# MCU.net
KiCad netlist of a schematic drawn in Altium Designer
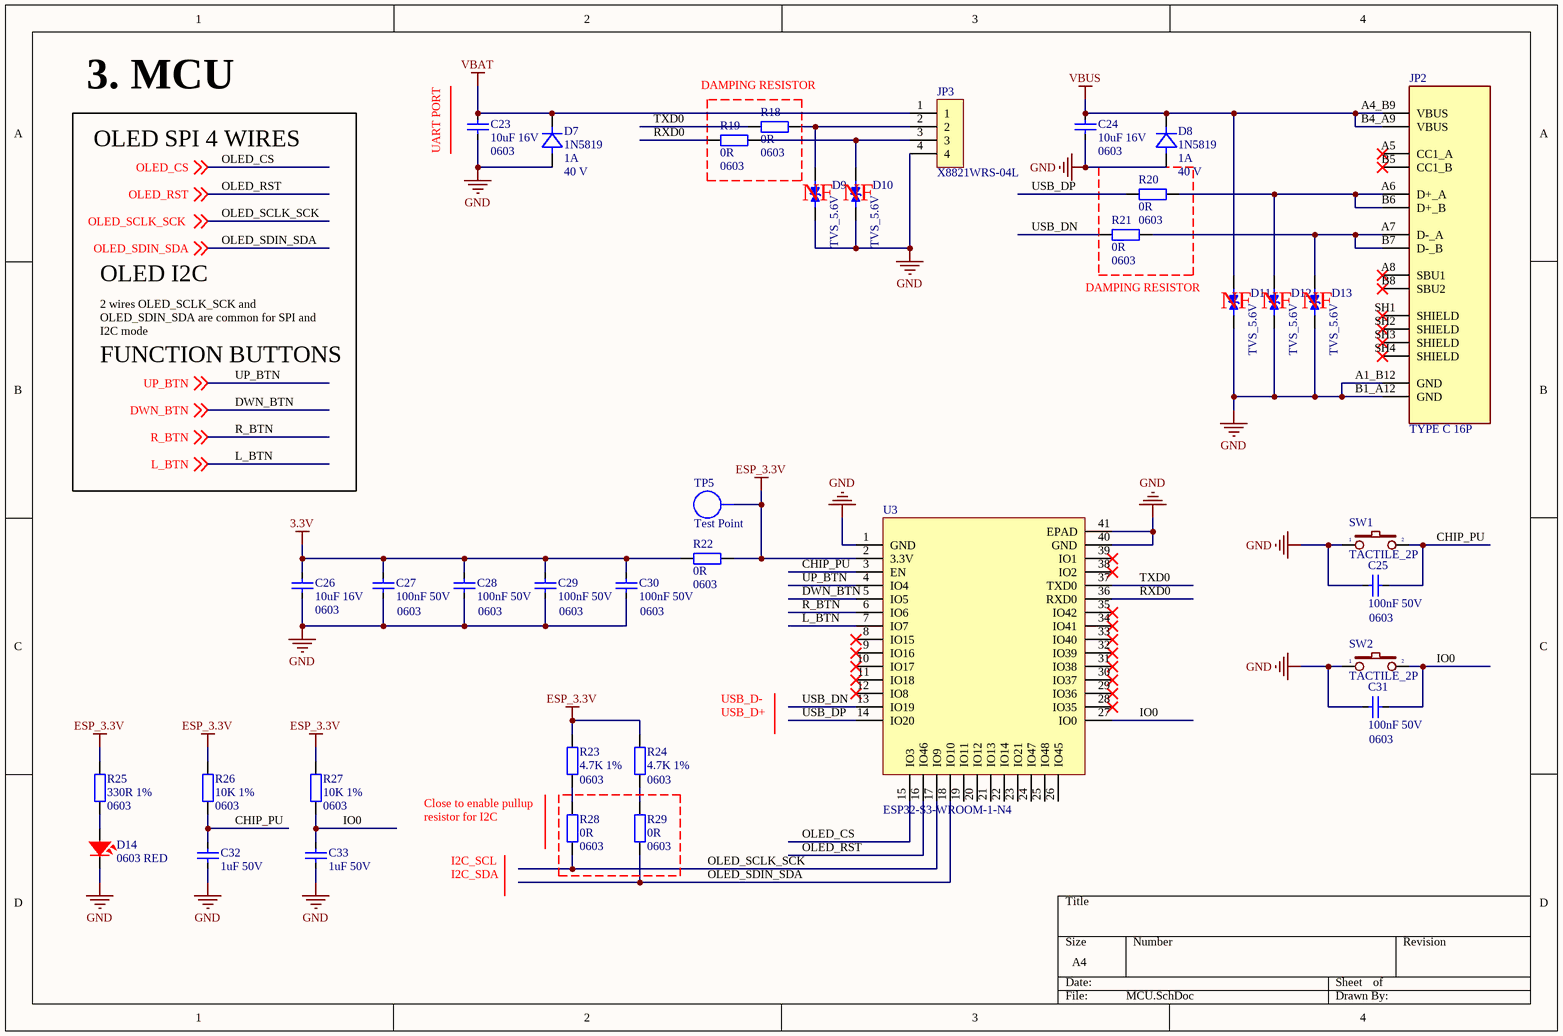
[diagram p0: MCU.SchDoc]

(export (version "E")
  (design (tool "Eeschema 10.0.6"))
  (components
    (comp (ref "C23")
      (value "10uF 16V")
      (footprint "CAP_SMD_0603")
      (description "10 µF ±20% 16V Ceramic Capacitor X6S 0603 (1608 Metric)")
      (fields
        (field (name "MANUFACTURER") "Murata Electronics")
        (field (name "MANUFACTURE PART NUMBER") "GRM188C81C106MA73D")
        (field (name "SIZE") "0603")
      )
      (libsource (lib "Capacitors") (part "C0603_MLCC_10uF_16V"))
    )
    (comp (ref "C24")
      (value "10uF 16V")
      (footprint "CAP_SMD_0603")
      (description "10 µF ±20% 16V Ceramic Capacitor X6S 0603 (1608 Metric)")
      (fields
        (field (name "MANUFACTURER") "Murata Electronics")
        (field (name "MANUFACTURE PART NUMBER") "GRM188C81C106MA73D")
        (field (name "SIZE") "0603")
      )
      (libsource (lib "Capacitors") (part "C0603_MLCC_10uF_16V"))
    )
    (comp (ref "C25")
      (value "100nF 50V")
      (footprint "CAP_SMD_0603")
      (description "0.1 µF ±10% 50V Ceramic Capacitor X7R 0603 (1608 Metric)")
      (fields
        (field (name "MANUFACTURER") "Samsung Electro-Mechanics")
        (field (name "MANUFACTURE PART NUMBER") "CL10B104KB8NNNC")
        (field (name "SIZE") "0603")
      )
      (libsource (lib "Capacitors") (part "C0603_MLCC_100nF_50V"))
    )
    (comp (ref "C26")
      (value "10uF 16V")
      (footprint "CAP_SMD_0603")
      (description "10 µF ±20% 16V Ceramic Capacitor X6S 0603 (1608 Metric)")
      (fields
        (field (name "MANUFACTURER") "Murata Electronics")
        (field (name "MANUFACTURE PART NUMBER") "GRM188C81C106MA73D")
        (field (name "SIZE") "0603")
      )
      (libsource (lib "Capacitors") (part "C0603_MLCC_10uF_16V"))
    )
    (comp (ref "C27")
      (value "100nF 50V")
      (footprint "CAP_SMD_0603")
      (description "0.1 µF ±10% 50V Ceramic Capacitor X7R 0603 (1608 Metric)")
      (fields
        (field (name "MANUFACTURER") "Samsung Electro-Mechanics")
        (field (name "MANUFACTURE PART NUMBER") "CL10B104KB8NNNC")
        (field (name "SIZE") "0603")
      )
      (libsource (lib "Capacitors") (part "C0603_MLCC_100nF_50V"))
    )
    (comp (ref "C28")
      (value "100nF 50V")
      (footprint "CAP_SMD_0603")
      (description "0.1 µF ±10% 50V Ceramic Capacitor X7R 0603 (1608 Metric)")
      (fields
        (field (name "MANUFACTURER") "Samsung Electro-Mechanics")
        (field (name "MANUFACTURE PART NUMBER") "CL10B104KB8NNNC")
        (field (name "SIZE") "0603")
      )
      (libsource (lib "Capacitors") (part "C0603_MLCC_100nF_50V"))
    )
    (comp (ref "C29")
      (value "100nF 50V")
      (footprint "CAP_SMD_0603")
      (description "0.1 µF ±10% 50V Ceramic Capacitor X7R 0603 (1608 Metric)")
      (fields
        (field (name "MANUFACTURER") "Samsung Electro-Mechanics")
        (field (name "MANUFACTURE PART NUMBER") "CL10B104KB8NNNC")
        (field (name "SIZE") "0603")
      )
      (libsource (lib "Capacitors") (part "C0603_MLCC_100nF_50V"))
    )
    (comp (ref "C30")
      (value "100nF 50V")
      (footprint "CAP_SMD_0603")
      (description "0.1 µF ±10% 50V Ceramic Capacitor X7R 0603 (1608 Metric)")
      (fields
        (field (name "MANUFACTURER") "Samsung Electro-Mechanics")
        (field (name "MANUFACTURE PART NUMBER") "CL10B104KB8NNNC")
        (field (name "SIZE") "0603")
      )
      (libsource (lib "Capacitors") (part "C0603_MLCC_100nF_50V"))
    )
    (comp (ref "C31")
      (value "100nF 50V")
      (footprint "CAP_SMD_0603")
      (description "0.1 µF ±10% 50V Ceramic Capacitor X7R 0603 (1608 Metric)")
      (fields
        (field (name "MANUFACTURER") "Samsung Electro-Mechanics")
        (field (name "MANUFACTURE PART NUMBER") "CL10B104KB8NNNC")
        (field (name "SIZE") "0603")
      )
      (libsource (lib "Capacitors") (part "C0603_MLCC_100nF_50V"))
    )
    (comp (ref "C32")
      (value "1uF 50V")
      (footprint "CAP_SMD_0603")
      (description "1 µF ±10% 50V Ceramic Capacitor X5R 0603 (1608 Metric)")
      (fields
        (field (name "MANUFACTURER") "Samsung Electro-Mechanics")
        (field (name "MANUFACTURE PART NUMBER") "CL10A105KB8NNNC")
      )
      (libsource (lib "Capacitors") (part "C0603_MLCC_1uF_50V"))
    )
    (comp (ref "C33")
      (value "1uF 50V")
      (footprint "CAP_SMD_0603")
      (description "1 µF ±10% 50V Ceramic Capacitor X5R 0603 (1608 Metric)")
      (fields
        (field (name "MANUFACTURER") "Samsung Electro-Mechanics")
        (field (name "MANUFACTURE PART NUMBER") "CL10A105KB8NNNC")
      )
      (libsource (lib "Capacitors") (part "C0603_MLCC_1uF_50V"))
    )
    (comp (ref "D7")
      (value "1N5819")
      (footprint "DIO-SMD-123")
      (description "Diode 40 V 1A Surface Mount SOD-123")
      (fields
        (field (name "MANUFACTURER") "Diodes Incorporated")
        (field (name "MANUFACTURE PART NUMBER") "1N5819HW-7-F")
        (field (name "CURRENT - AVERAGE RECTIFIED (IO)") "1A")
        (field (name "VOLTAGE - DC REVERSE (VR) (MAX)") "40 V")
      )
      (libsource (lib "Diode") (part "1N5819"))
    )
    (comp (ref "D8")
      (value "1N5819")
      (footprint "DIO-SMD-123")
      (description "Diode 40 V 1A Surface Mount SOD-123")
      (fields
        (field (name "MANUFACTURER") "Diodes Incorporated")
        (field (name "MANUFACTURE PART NUMBER") "1N5819HW-7-F")
        (field (name "CURRENT - AVERAGE RECTIFIED (IO)") "1A")
        (field (name "VOLTAGE - DC REVERSE (VR) (MAX)") "40 V")
      )
      (libsource (lib "Diode") (part "1N5819"))
    )
    (comp (ref "D9")
      (value "TVS_5.6V")
      (footprint "SOD_523")
      (description "9.4A 18.6V 5.6V Bi-Directional 5V SOD-523 Electrostatic and Surge Protection (TVS/ESD) ROHS")
      (fields (field (name "MANUFACTURER") "LRC") (field (name "MANUFACTURE PART NUMBER") "LESD5D5.0CT1G"))
      (libsource (lib "Diode") (part "TVS_5.6V"))
    )
    (comp (ref "D10")
      (value "TVS_5.6V")
      (footprint "SOD_523")
      (description "9.4A 18.6V 5.6V Bi-Directional 5V SOD-523 Electrostatic and Surge Protection (TVS/ESD) ROHS")
      (fields (field (name "MANUFACTURER") "LRC") (field (name "MANUFACTURE PART NUMBER") "LESD5D5.0CT1G"))
      (libsource (lib "Diode") (part "TVS_5.6V"))
    )
    (comp (ref "D11")
      (value "TVS_5.6V")
      (footprint "SOD_523")
      (description "9.4A 18.6V 5.6V Bi-Directional 5V SOD-523 Electrostatic and Surge Protection (TVS/ESD) ROHS")
      (fields (field (name "MANUFACTURER") "LRC") (field (name "MANUFACTURE PART NUMBER") "LESD5D5.0CT1G"))
      (libsource (lib "Diode") (part "TVS_5.6V"))
    )
    (comp (ref "D12")
      (value "TVS_5.6V")
      (footprint "SOD_523")
      (description "9.4A 18.6V 5.6V Bi-Directional 5V SOD-523 Electrostatic and Surge Protection (TVS/ESD) ROHS")
      (fields (field (name "MANUFACTURER") "LRC") (field (name "MANUFACTURE PART NUMBER") "LESD5D5.0CT1G"))
      (libsource (lib "Diode") (part "TVS_5.6V"))
    )
    (comp (ref "D13")
      (value "TVS_5.6V")
      (footprint "SOD_523")
      (description "9.4A 18.6V 5.6V Bi-Directional 5V SOD-523 Electrostatic and Surge Protection (TVS/ESD) ROHS")
      (fields (field (name "MANUFACTURER") "LRC") (field (name "MANUFACTURE PART NUMBER") "LESD5D5.0CT1G"))
      (libsource (lib "Diode") (part "TVS_5.6V"))
    )
    (comp (ref "D14")
      (value "0603 RED")
      (footprint "LED-0603")
      (description "Red 625nm LED Indication - Discrete 2V 0603 (1608 Metric)")
      (fields
        (field (name "MANUFACTURER") "Würth Elektronik")
        (field (name "MANUFACTURE PART NUMBER") "150060RS75000")
      )
      (libsource (lib "LEDs") (part "LED_0603_RED"))
    )
    (comp (ref "JP2")
      (value "TYPE C 16P")
      (footprint "TYPE C 16P")
      (fields
        (field (name "MANUFACTURER") "Amphenol ICC (Commercial Products)")
        (field (name "MANUFACTURE PART NUMBER") "12402012E212A")
      )
      (libsource (lib "Connectors") (part "TYPE_C_16P"))
    )
    (comp (ref "JP3")
      (value "X8821WRS-04L")
      (footprint "CONN_X8821WRS-04L-LPSN")
      (fields
        (field (name "MANUFACTURER") "XKB Connection")
        (field (name "MANUFACTURE PART NUMBER") "X8821WRS-04-9TSN")
      )
      (libsource (lib "Connectors") (part "X8821WRS-04L"))
    )
    (comp (ref "R18")
      (value "0R")
      (footprint "RES_SMD_0603")
      (description "0 Ohms Jumper Chip Resistor 0603 (1608 Metric) Automotive AEC-Q200 Thick Film")
      (fields
        (field (name "MANUFACTURER") "Stackpole Electronics Inc")
        (field (name "MANUFACTURE PART NUMBER") "RMCF0603ZT0R00")
        (field (name "SIZE") "0603")
      )
      (libsource (lib "Resistors") (part "R0603_0R"))
    )
    (comp (ref "R19")
      (value "0R")
      (footprint "RES_SMD_0603")
      (description "0 Ohms Jumper Chip Resistor 0603 (1608 Metric) Automotive AEC-Q200 Thick Film")
      (fields
        (field (name "MANUFACTURER") "Stackpole Electronics Inc")
        (field (name "MANUFACTURE PART NUMBER") "RMCF0603ZT0R00")
        (field (name "SIZE") "0603")
      )
      (libsource (lib "Resistors") (part "R0603_0R"))
    )
    (comp (ref "R20")
      (value "0R")
      (footprint "RES_SMD_0603")
      (description "0 Ohms Jumper Chip Resistor 0603 (1608 Metric) Automotive AEC-Q200 Thick Film")
      (fields
        (field (name "MANUFACTURER") "Stackpole Electronics Inc")
        (field (name "MANUFACTURE PART NUMBER") "RMCF0603ZT0R00")
        (field (name "SIZE") "0603")
      )
      (libsource (lib "Resistors") (part "R0603_0R"))
    )
    (comp (ref "R21")
      (value "0R")
      (footprint "RES_SMD_0603")
      (description "0 Ohms Jumper Chip Resistor 0603 (1608 Metric) Automotive AEC-Q200 Thick Film")
      (fields
        (field (name "MANUFACTURER") "Stackpole Electronics Inc")
        (field (name "MANUFACTURE PART NUMBER") "RMCF0603ZT0R00")
        (field (name "SIZE") "0603")
      )
      (libsource (lib "Resistors") (part "R0603_0R"))
    )
    (comp (ref "R22")
      (value "0R")
      (footprint "RES_SMD_0603")
      (description "0 Ohms Jumper Chip Resistor 0603 (1608 Metric) Automotive AEC-Q200 Thick Film")
      (fields
        (field (name "MANUFACTURER") "Stackpole Electronics Inc")
        (field (name "MANUFACTURE PART NUMBER") "RMCF0603ZT0R00")
        (field (name "SIZE") "0603")
      )
      (libsource (lib "Resistors") (part "R0603_0R"))
    )
    (comp (ref "R23")
      (value "4.7K 1%")
      (footprint "RES_SMD_0603")
      (description "4.7 kOhms ±1% 0.1W, 1/10W Chip Resistor 0603 (1608 Metric) Moisture Resistant Thick Film")
      (fields
        (field (name "MANUFACTURER") "YAGEO")
        (field (name "MANUFACTURE PART NUMBER") "RC0603FR-074K7L")
        (field (name "SIZE") "0603")
      )
      (libsource (lib "Resistors") (part "R0603_4.7K"))
    )
    (comp (ref "R24")
      (value "4.7K 1%")
      (footprint "RES_SMD_0603")
      (description "4.7 kOhms ±1% 0.1W, 1/10W Chip Resistor 0603 (1608 Metric) Moisture Resistant Thick Film")
      (fields
        (field (name "MANUFACTURER") "YAGEO")
        (field (name "MANUFACTURE PART NUMBER") "RC0603FR-074K7L")
        (field (name "SIZE") "0603")
      )
      (libsource (lib "Resistors") (part "R0603_4.7K"))
    )
    (comp (ref "R25")
      (value "330R 1%")
      (footprint "RES_SMD_0603")
      (description "330 Ohms ±1% 0.1W, 1/10W Chip Resistor 0603 (1608 Metric) Thick Film")
      (fields
        (field (name "MANUFACTURER") "TE Connectivity Passive Product")
        (field (name "MANUFACTURE PART NUMBER") "CRG0603F330R")
        (field (name "SIZE") "0603")
      )
      (libsource (lib "Resistors") (part "R0603_330R"))
    )
    (comp (ref "R26")
      (value "10K 1%")
      (footprint "RES_SMD_0603")
      (description "10 kOhms ±1% 0.1W, 1/10W Chip Resistor 0603 (1608 Metric) Moisture Resistant Thick Film")
      (fields
        (field (name "MANUFACTURER") "YAGEO")
        (field (name "MANUFACTURE PART NUMBER") "RC0603FR-0710KL")
        (field (name "SIZE") "0603")
      )
      (libsource (lib "Resistors") (part "R0603_10K"))
    )
    (comp (ref "R27")
      (value "10K 1%")
      (footprint "RES_SMD_0603")
      (description "10 kOhms ±1% 0.1W, 1/10W Chip Resistor 0603 (1608 Metric) Moisture Resistant Thick Film")
      (fields
        (field (name "MANUFACTURER") "YAGEO")
        (field (name "MANUFACTURE PART NUMBER") "RC0603FR-0710KL")
        (field (name "SIZE") "0603")
      )
      (libsource (lib "Resistors") (part "R0603_10K"))
    )
    (comp (ref "R28")
      (value "0R")
      (footprint "RES_SMD_0603")
      (description "0 Ohms Jumper Chip Resistor 0603 (1608 Metric) Automotive AEC-Q200 Thick Film")
      (fields
        (field (name "MANUFACTURER") "Stackpole Electronics Inc")
        (field (name "MANUFACTURE PART NUMBER") "RMCF0603ZT0R00")
        (field (name "SIZE") "0603")
      )
      (libsource (lib "Resistors") (part "R0603_0R"))
    )
    (comp (ref "R29")
      (value "0R")
      (footprint "RES_SMD_0603")
      (description "0 Ohms Jumper Chip Resistor 0603 (1608 Metric) Automotive AEC-Q200 Thick Film")
      (fields
        (field (name "MANUFACTURER") "Stackpole Electronics Inc")
        (field (name "MANUFACTURE PART NUMBER") "RMCF0603ZT0R00")
        (field (name "SIZE") "0603")
      )
      (libsource (lib "Resistors") (part "R0603_0R"))
    )
    (comp (ref "SW1")
      (value "TACTILE_2P")
      (footprint "C&K SW 2P")
      (description "Tactile Switch SPST-NO Top Actuated Surface Mount")
      (fields
        (field (name "MANUFACTURER") "C&K")
        (field (name "MANUFACTURE PART NUMBER") "PTS636 SM25F SMTR LFS")
      )
      (libsource (lib "Button") (part "SWITCH_TACTILE_SPST"))
    )
    (comp (ref "SW2")
      (value "TACTILE_2P")
      (footprint "C&K SW 2P")
      (description "Tactile Switch SPST-NO Top Actuated Surface Mount")
      (fields
        (field (name "MANUFACTURER") "C&K")
        (field (name "MANUFACTURE PART NUMBER") "PTS636 SM25F SMTR LFS")
      )
      (libsource (lib "Button") (part "SWITCH_TACTILE_SPST"))
    )
    (comp (ref "TP5")
      (value "Test Point")
      (footprint "TEST_POINT")
      (libsource (lib "Connectors") (part "TEST_POINT"))
    )
    (comp (ref "U3")
      (value "ESP32-S3-WROOM-1-N4")
      (footprint "ESP32-S3-WROOM-1")
      (description "SMD,18x25.5mm WiFi Modules ROHS")
      (fields (field (name "MANUFACTURER") "Espressif Systems"))
      (libsource (lib "MCU") (part "ESP32-S3-WROOM-1-N4"))
    )
  )
  (nets
    (net (code "1") (name "/CHIP_PU") (class "Default")
      (node (ref "C25") (pin "2") (pinfunction "2_2") (pintype "passive"))
      (node (ref "C32") (pin "2") (pinfunction "2_2") (pintype "passive"))
      (node (ref "R26") (pin "1") (pinfunction "1_1") (pintype "passive"))
      (node (ref "SW1") (pin "2") (pinfunction "2_2") (pintype "passive"))
      (node (ref "U3") (pin "3") (pinfunction "EN_3") (pintype "passive"))
    )
    (net (code "2") (name "/IO0") (class "Default")
      (node (ref "C31") (pin "2") (pinfunction "2_2") (pintype "passive"))
      (node (ref "C33") (pin "2") (pinfunction "2_2") (pintype "passive"))
      (node (ref "R27") (pin "1") (pinfunction "1_1") (pintype "passive"))
      (node (ref "SW2") (pin "2") (pinfunction "2_2") (pintype "passive"))
      (node (ref "U3") (pin "27") (pinfunction "IO0_27") (pintype "passive"))
    )
    (net (code "3") (name "/RXD0") (class "Default")
      (node (ref "R19") (pin "2") (pinfunction "2_2") (pintype "passive"))
      (node (ref "U3") (pin "36") (pinfunction "RXD0_36") (pintype "passive"))
    )
    (net (code "4") (name "/TXD0") (class "Default")
      (node (ref "R18") (pin "2") (pinfunction "2_2") (pintype "passive"))
      (node (ref "U3") (pin "37") (pinfunction "TXD0_37") (pintype "passive"))
    )
    (net (code "5") (name "/USB_DN") (class "Default")
      (node (ref "R21") (pin "2") (pinfunction "2_2") (pintype "passive"))
      (node (ref "U3") (pin "13") (pinfunction "IO19_13") (pintype "passive"))
    )
    (net (code "6") (name "/USB_DP") (class "Default")
      (node (ref "R20") (pin "2") (pinfunction "2_2") (pintype "passive"))
      (node (ref "U3") (pin "14") (pinfunction "IO20_14") (pintype "passive"))
    )
    (net (code "7") (name "3.3V") (class "Default")
      (node (ref "C26") (pin "1") (pinfunction "1_1") (pintype "passive"))
      (node (ref "C27") (pin "2") (pinfunction "2_2") (pintype "passive"))
      (node (ref "C28") (pin "2") (pinfunction "2_2") (pintype "passive"))
      (node (ref "C29") (pin "2") (pinfunction "2_2") (pintype "passive"))
      (node (ref "C30") (pin "2") (pinfunction "2_2") (pintype "passive"))
      (node (ref "R22") (pin "2") (pinfunction "2_2") (pintype "passive"))
    )
    (net (code "8") (name "DWN_BTN") (class "Default")
      (node (ref "U3") (pin "5") (pinfunction "IO5_5") (pintype "passive"))
    )
    (net (code "9") (name "ESP_3.3V") (class "Default")
      (node (ref "R22") (pin "1") (pinfunction "1_1") (pintype "passive"))
      (node (ref "R23") (pin "2") (pinfunction "2_2") (pintype "passive"))
      (node (ref "R24") (pin "2") (pinfunction "2_2") (pintype "passive"))
      (node (ref "R25") (pin "1") (pinfunction "1_1") (pintype "passive"))
      (node (ref "R26") (pin "2") (pinfunction "2_2") (pintype "passive"))
      (node (ref "R27") (pin "2") (pinfunction "2_2") (pintype "passive"))
      (node (ref "TP5") (pin "1") (pinfunction "1_1") (pintype "passive"))
      (node (ref "U3") (pin "2") (pinfunction "3.3V_2") (pintype "passive"))
    )
    (net (code "10") (name "GND") (class "Default")
      (node (ref "C23") (pin "2") (pinfunction "2_2") (pintype "passive"))
      (node (ref "C24") (pin "2") (pinfunction "2_2") (pintype "passive"))
      (node (ref "C25") (pin "1") (pinfunction "1_1") (pintype "passive"))
      (node (ref "C26") (pin "2") (pinfunction "2_2") (pintype "passive"))
      (node (ref "C27") (pin "1") (pinfunction "1_1") (pintype "passive"))
      (node (ref "C28") (pin "1") (pinfunction "1_1") (pintype "passive"))
      (node (ref "C29") (pin "1") (pinfunction "1_1") (pintype "passive"))
      (node (ref "C30") (pin "1") (pinfunction "1_1") (pintype "passive"))
      (node (ref "C31") (pin "1") (pinfunction "1_1") (pintype "passive"))
      (node (ref "C32") (pin "1") (pinfunction "1_1") (pintype "passive"))
      (node (ref "C33") (pin "1") (pinfunction "1_1") (pintype "passive"))
      (node (ref "D10") (pin "1") (pinfunction "1_1") (pintype "passive"))
      (node (ref "D11") (pin "1") (pinfunction "1_1") (pintype "passive"))
      (node (ref "D12") (pin "1") (pinfunction "1_1") (pintype "passive"))
      (node (ref "D13") (pin "1") (pinfunction "1_1") (pintype "passive"))
      (node (ref "D14") (pin "2") (pinfunction "2_2") (pintype "passive"))
      (node (ref "D7") (pin "A") (pinfunction "A_A") (pintype "passive"))
      (node (ref "D8") (pin "A") (pinfunction "A_A") (pintype "passive"))
      (node (ref "D9") (pin "1") (pinfunction "1_1") (pintype "passive"))
      (node (ref "JP2") (pin "A1_B12") (pinfunction "GND_A1_B12") (pintype "passive"))
      (node (ref "JP2") (pin "B1_A12") (pinfunction "GND_B1_A12") (pintype "passive"))
      (node (ref "JP3") (pin "4") (pinfunction "4_4") (pintype "passive"))
      (node (ref "SW1") (pin "1") (pinfunction "1_1") (pintype "passive"))
      (node (ref "SW2") (pin "1") (pinfunction "1_1") (pintype "passive"))
      (node (ref "U3") (pin "1") (pinfunction "GND_1") (pintype "passive"))
      (node (ref "U3") (pin "40") (pinfunction "GND_40") (pintype "passive"))
      (node (ref "U3") (pin "41") (pinfunction "EPAD_41") (pintype "passive"))
    )
    (net (code "11") (name "L_BTN") (class "Default")
      (node (ref "U3") (pin "7") (pinfunction "IO7_7") (pintype "passive"))
    )
    (net (code "12") (name "Net-(D9-Pad2)") (class "Default")
      (node (ref "D9") (pin "2") (pinfunction "2_2") (pintype "passive"))
      (node (ref "JP3") (pin "2") (pinfunction "2_2") (pintype "passive"))
      (node (ref "R18") (pin "1") (pinfunction "1_1") (pintype "passive"))
    )
    (net (code "13") (name "Net-(D10-Pad2)") (class "Default")
      (node (ref "D10") (pin "2") (pinfunction "2_2") (pintype "passive"))
      (node (ref "JP3") (pin "3") (pinfunction "3_3") (pintype "passive"))
      (node (ref "R19") (pin "1") (pinfunction "1_1") (pintype "passive"))
    )
    (net (code "14") (name "Net-(D14-Pad1)") (class "Default")
      (node (ref "D14") (pin "1") (pinfunction "1_1") (pintype "passive"))
      (node (ref "R25") (pin "2") (pinfunction "2_2") (pintype "passive"))
    )
    (net (code "15") (name "Net-(JP2-D+_A)") (class "Default")
      (node (ref "D12") (pin "2") (pinfunction "2_2") (pintype "passive"))
      (node (ref "JP2") (pin "A6") (pinfunction "D+_A_A6") (pintype "passive"))
      (node (ref "JP2") (pin "B6") (pinfunction "D+_B_B6") (pintype "passive"))
      (node (ref "R20") (pin "1") (pinfunction "1_1") (pintype "passive"))
    )
    (net (code "16") (name "Net-(JP2-D-_A)") (class "Default")
      (node (ref "D13") (pin "2") (pinfunction "2_2") (pintype "passive"))
      (node (ref "JP2") (pin "A7") (pinfunction "D-_A_A7") (pintype "passive"))
      (node (ref "JP2") (pin "B7") (pinfunction "D-_B_B7") (pintype "passive"))
      (node (ref "R21") (pin "1") (pinfunction "1_1") (pintype "passive"))
    )
    (net (code "17") (name "Net-(R23-Pad1)") (class "Default")
      (node (ref "R23") (pin "1") (pinfunction "1_1") (pintype "passive"))
      (node (ref "R28") (pin "1") (pinfunction "1_1") (pintype "passive"))
    )
    (net (code "18") (name "Net-(R24-Pad1)") (class "Default")
      (node (ref "R24") (pin "1") (pinfunction "1_1") (pintype "passive"))
      (node (ref "R29") (pin "1") (pinfunction "1_1") (pintype "passive"))
    )
    (net (code "19") (name "OLED_CS") (class "Default")
      (node (ref "U3") (pin "15") (pinfunction "IO3_15") (pintype "passive"))
    )
    (net (code "20") (name "OLED_RST") (class "Default")
      (node (ref "U3") (pin "16") (pinfunction "IO46_16") (pintype "passive"))
    )
    (net (code "21") (name "OLED_SCLK_SCK") (class "Default")
      (node (ref "R28") (pin "2") (pinfunction "2_2") (pintype "passive"))
      (node (ref "U3") (pin "17") (pinfunction "IO9_17") (pintype "passive"))
    )
    (net (code "22") (name "OLED_SDIN_SDA") (class "Default")
      (node (ref "R29") (pin "2") (pinfunction "2_2") (pintype "passive"))
      (node (ref "U3") (pin "18") (pinfunction "IO10_18") (pintype "passive"))
    )
    (net (code "23") (name "R_BTN") (class "Default")
      (node (ref "U3") (pin "6") (pinfunction "IO6_6") (pintype "passive"))
    )
    (net (code "24") (name "UP_BTN") (class "Default")
      (node (ref "U3") (pin "4") (pinfunction "IO4_4") (pintype "passive"))
    )
    (net (code "25") (name "VBAT") (class "Default")
      (node (ref "C23") (pin "1") (pinfunction "1_1") (pintype "passive"))
      (node (ref "D7") (pin "C") (pinfunction "C_C") (pintype "passive"))
      (node (ref "JP3") (pin "1") (pinfunction "1_1") (pintype "passive"))
    )
    (net (code "26") (name "VBUS") (class "Default")
      (node (ref "C24") (pin "1") (pinfunction "1_1") (pintype "passive"))
      (node (ref "D11") (pin "2") (pinfunction "2_2") (pintype "passive"))
      (node (ref "D8") (pin "C") (pinfunction "C_C") (pintype "passive"))
      (node (ref "JP2") (pin "A4_B9") (pinfunction "VBUS_A4_B9") (pintype "passive"))
      (node (ref "JP2") (pin "B4_A9") (pinfunction "VBUS_B4_A9") (pintype "passive"))
    )
    (net (code "27") (name "unconnected-(JP2-CC1_A-PadA5)") (class "Default")
      (node (ref "JP2") (pin "A5") (pinfunction "CC1_A_A5") (pintype "passive+no_connect"))
    )
    (net (code "28") (name "unconnected-(JP2-CC1_B-PadB5)") (class "Default")
      (node (ref "JP2") (pin "B5") (pinfunction "CC1_B_B5") (pintype "passive+no_connect"))
    )
    (net (code "29") (name "unconnected-(JP2-SBU1-PadA8)") (class "Default")
      (node (ref "JP2") (pin "A8") (pinfunction "SBU1_A8") (pintype "passive+no_connect"))
    )
    (net (code "30") (name "unconnected-(JP2-SBU2-PadB8)") (class "Default")
      (node (ref "JP2") (pin "B8") (pinfunction "SBU2_B8") (pintype "passive+no_connect"))
    )
    (net (code "31") (name "unconnected-(JP2-SHIELD-PadSH1)") (class "Default")
      (node (ref "JP2") (pin "SH1") (pinfunction "SHIELD_SH1") (pintype "passive+no_connect"))
    )
    (net (code "32") (name "unconnected-(JP2-SHIELD-PadSH2)") (class "Default")
      (node (ref "JP2") (pin "SH2") (pinfunction "SHIELD_SH2") (pintype "passive+no_connect"))
    )
    (net (code "33") (name "unconnected-(JP2-SHIELD-PadSH3)") (class "Default")
      (node (ref "JP2") (pin "SH3") (pinfunction "SHIELD_SH3") (pintype "passive+no_connect"))
    )
    (net (code "34") (name "unconnected-(JP2-SHIELD-PadSH4)") (class "Default")
      (node (ref "JP2") (pin "SH4") (pinfunction "SHIELD_SH4") (pintype "passive+no_connect"))
    )
    (net (code "35") (name "unconnected-(U3-IO1-Pad39)") (class "Default")
      (node (ref "U3") (pin "39") (pinfunction "IO1_39") (pintype "passive+no_connect"))
    )
    (net (code "36") (name "unconnected-(U3-IO2-Pad38)") (class "Default")
      (node (ref "U3") (pin "38") (pinfunction "IO2_38") (pintype "passive+no_connect"))
    )
    (net (code "37") (name "unconnected-(U3-IO8-Pad12)") (class "Default")
      (node (ref "U3") (pin "12") (pinfunction "IO8_12") (pintype "passive+no_connect"))
    )
    (net (code "38") (name "unconnected-(U3-IO11-Pad19)") (class "Default")
      (node (ref "U3") (pin "19") (pinfunction "IO11_19") (pintype "passive"))
    )
    (net (code "39") (name "unconnected-(U3-IO12-Pad20)") (class "Default")
      (node (ref "U3") (pin "20") (pinfunction "IO12_20") (pintype "passive"))
    )
    (net (code "40") (name "unconnected-(U3-IO13-Pad21)") (class "Default")
      (node (ref "U3") (pin "21") (pinfunction "IO13_21") (pintype "passive"))
    )
    (net (code "41") (name "unconnected-(U3-IO14-Pad22)") (class "Default")
      (node (ref "U3") (pin "22") (pinfunction "IO14_22") (pintype "passive"))
    )
    (net (code "42") (name "unconnected-(U3-IO15-Pad8)") (class "Default")
      (node (ref "U3") (pin "8") (pinfunction "IO15_8") (pintype "passive+no_connect"))
    )
    (net (code "43") (name "unconnected-(U3-IO16-Pad9)") (class "Default")
      (node (ref "U3") (pin "9") (pinfunction "IO16_9") (pintype "passive+no_connect"))
    )
    (net (code "44") (name "unconnected-(U3-IO17-Pad10)") (class "Default")
      (node (ref "U3") (pin "10") (pinfunction "IO17_10") (pintype "passive+no_connect"))
    )
    (net (code "45") (name "unconnected-(U3-IO18-Pad11)") (class "Default")
      (node (ref "U3") (pin "11") (pinfunction "IO18_11") (pintype "passive+no_connect"))
    )
    (net (code "46") (name "unconnected-(U3-IO21-Pad23)") (class "Default")
      (node (ref "U3") (pin "23") (pinfunction "IO21_23") (pintype "passive"))
    )
    (net (code "47") (name "unconnected-(U3-IO35-Pad28)") (class "Default")
      (node (ref "U3") (pin "28") (pinfunction "IO35_28") (pintype "passive+no_connect"))
    )
    (net (code "48") (name "unconnected-(U3-IO36-Pad29)") (class "Default")
      (node (ref "U3") (pin "29") (pinfunction "IO36_29") (pintype "passive+no_connect"))
    )
    (net (code "49") (name "unconnected-(U3-IO37-Pad30)") (class "Default")
      (node (ref "U3") (pin "30") (pinfunction "IO37_30") (pintype "passive+no_connect"))
    )
    (net (code "50") (name "unconnected-(U3-IO38-Pad31)") (class "Default")
      (node (ref "U3") (pin "31") (pinfunction "IO38_31") (pintype "passive+no_connect"))
    )
    (net (code "51") (name "unconnected-(U3-IO39-Pad32)") (class "Default")
      (node (ref "U3") (pin "32") (pinfunction "IO39_32") (pintype "passive+no_connect"))
    )
    (net (code "52") (name "unconnected-(U3-IO40-Pad33)") (class "Default")
      (node (ref "U3") (pin "33") (pinfunction "IO40_33") (pintype "passive+no_connect"))
    )
    (net (code "53") (name "unconnected-(U3-IO41-Pad34)") (class "Default")
      (node (ref "U3") (pin "34") (pinfunction "IO41_34") (pintype "passive+no_connect"))
    )
    (net (code "54") (name "unconnected-(U3-IO42-Pad35)") (class "Default")
      (node (ref "U3") (pin "35") (pinfunction "IO42_35") (pintype "passive+no_connect"))
    )
    (net (code "55") (name "unconnected-(U3-IO45-Pad26)") (class "Default")
      (node (ref "U3") (pin "26") (pinfunction "IO45_26") (pintype "passive"))
    )
    (net (code "56") (name "unconnected-(U3-IO47-Pad24)") (class "Default")
      (node (ref "U3") (pin "24") (pinfunction "IO47_24") (pintype "passive"))
    )
    (net (code "57") (name "unconnected-(U3-IO48-Pad25)") (class "Default")
      (node (ref "U3") (pin "25") (pinfunction "IO48_25") (pintype "passive"))
    )
  )
)
